# Cable.net
KiCad netlist of a schematic drawn in EAGLE
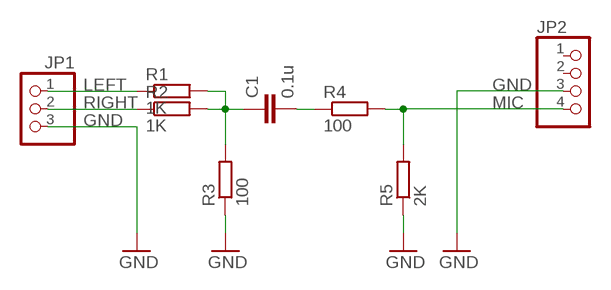
[diagram p0: schematic, sheet 1]

(export (version "E")
  (design (tool "Eeschema 10.0.6"))
  (components
    (comp (ref "C1")
      (value "0.1u")
      (footprint "eagle-import:C025-025X050")
      (libsource (lib "eagle-import") (part "C-EU025-025X050"))
    )
    (comp (ref "JP1")
      (value "PINHD-1X3")
      (footprint "eagle-import:1X03")
      (libsource (lib "eagle-import") (part "PINHD-1X3"))
    )
    (comp (ref "JP2")
      (value "PINHD-1X4")
      (footprint "eagle-import:1X04")
      (libsource (lib "eagle-import") (part "PINHD-1X4"))
    )
    (comp (ref "R1")
      (value "1K")
      (footprint "eagle-import:0204_7")
      (libsource (lib "eagle-import") (part "R-EU_0204/7"))
    )
    (comp (ref "R2")
      (value "1K")
      (footprint "eagle-import:0204_7")
      (libsource (lib "eagle-import") (part "R-EU_0204/7"))
    )
    (comp (ref "R3")
      (value "100")
      (footprint "eagle-import:0204_5")
      (libsource (lib "eagle-import") (part "R-EU_0204/5"))
    )
    (comp (ref "R4")
      (value "100")
      (footprint "eagle-import:0204_5")
      (libsource (lib "eagle-import") (part "R-EU_0204/5"))
    )
    (comp (ref "R5")
      (value "2K")
      (footprint "eagle-import:0204_7")
      (libsource (lib "eagle-import") (part "R-EU_0204/7"))
    )
  )
  (nets
    (net (code "1") (name "/LEFT") (class "Default")
      (node (ref "JP1") (pin "1") (pinfunction "1_1") (pintype "passive"))
      (node (ref "R1") (pin "1") (pinfunction "1_1") (pintype "passive"))
    )
    (net (code "2") (name "/MIC") (class "Default")
      (node (ref "JP2") (pin "4") (pinfunction "4_4") (pintype "passive"))
      (node (ref "R4") (pin "2") (pinfunction "2_2") (pintype "passive"))
      (node (ref "R5") (pin "2") (pinfunction "2_2") (pintype "passive"))
    )
    (net (code "3") (name "/RIGHT") (class "Default")
      (node (ref "JP1") (pin "2") (pinfunction "2_2") (pintype "passive"))
      (node (ref "R2") (pin "1") (pinfunction "1_1") (pintype "passive"))
    )
    (net (code "4") (name "GND") (class "Default")
      (node (ref "JP1") (pin "3") (pinfunction "3_3") (pintype "passive"))
      (node (ref "JP2") (pin "3") (pinfunction "3_3") (pintype "passive"))
      (node (ref "R3") (pin "1") (pinfunction "1_1") (pintype "passive"))
      (node (ref "R5") (pin "1") (pinfunction "1_1") (pintype "passive"))
    )
    (net (code "5") (name "Net-(C1-Pad1)") (class "Default")
      (node (ref "C1") (pin "1") (pinfunction "1_1") (pintype "passive"))
      (node (ref "R1") (pin "2") (pinfunction "2_2") (pintype "passive"))
      (node (ref "R2") (pin "2") (pinfunction "2_2") (pintype "passive"))
      (node (ref "R3") (pin "2") (pinfunction "2_2") (pintype "passive"))
    )
    (net (code "6") (name "Net-(C1-Pad2)") (class "Default")
      (node (ref "C1") (pin "2") (pinfunction "2_2") (pintype "passive"))
      (node (ref "R4") (pin "1") (pinfunction "1_1") (pintype "passive"))
    )
    (net (code "7") (name "unconnected-(JP2-Pad1)") (class "Default")
      (node (ref "JP2") (pin "1") (pinfunction "1_1") (pintype "passive"))
    )
    (net (code "8") (name "unconnected-(JP2-Pad2)") (class "Default")
      (node (ref "JP2") (pin "2") (pinfunction "2_2") (pintype "passive"))
    )
  )
)
